# AEGIS_Junction_Box.net
KiCad netlist of a schematic drawn in Altium Designer
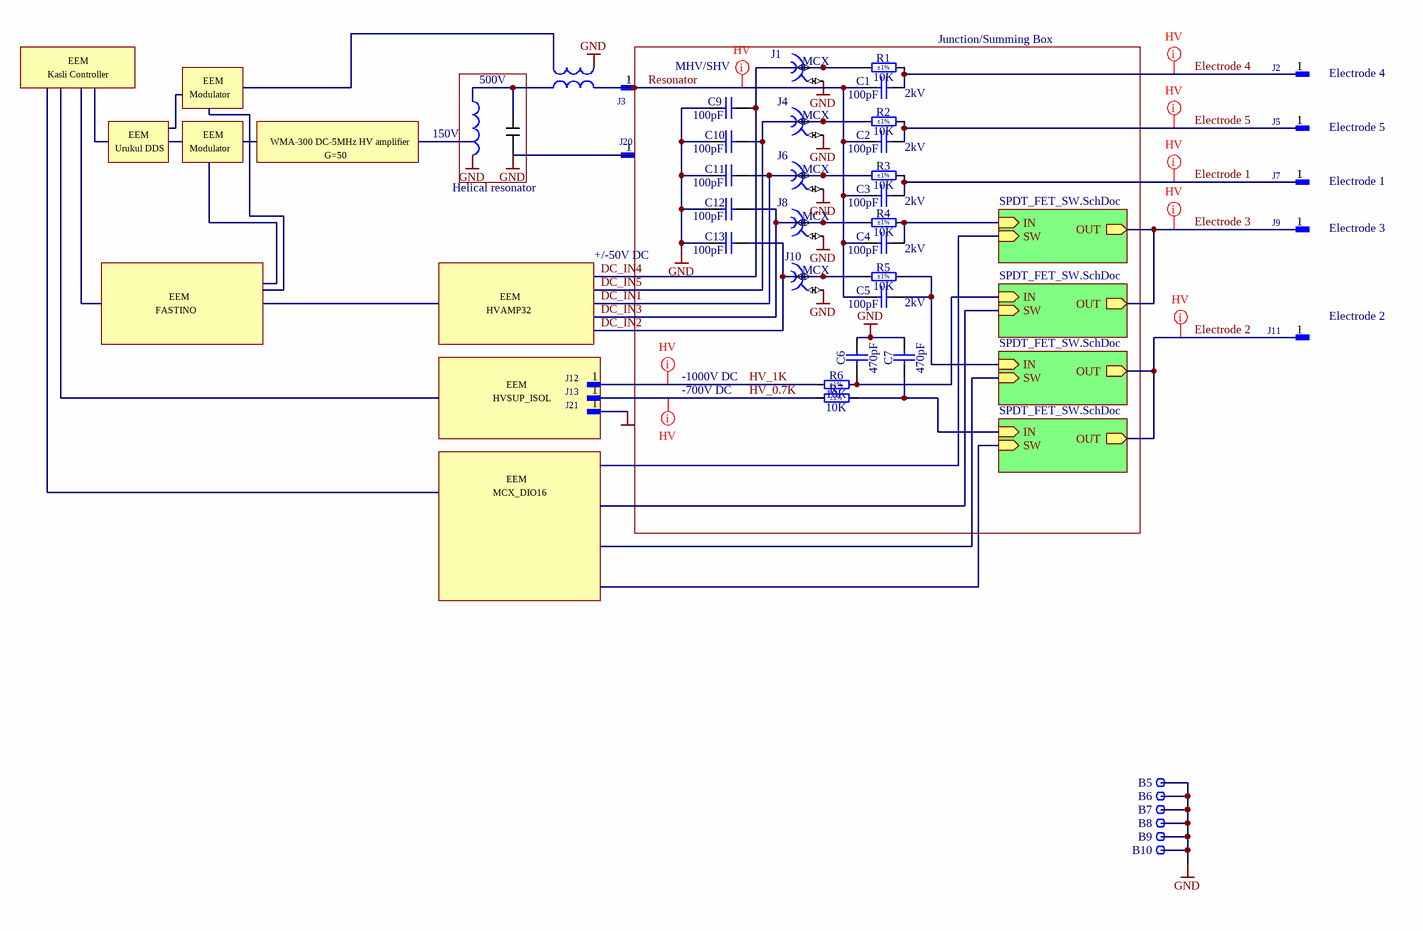
[diagram p0: AEGIS_Junction_Box.SchDoc]

(export (version "E")
  (design (tool "Eeschema 10.0.6"))
  (components
    (comp (ref "B5")
      (value "Plated Hole")
      (footprint "MTG320_550")
      (description "Single Terminal Socket")
      (fields (field (name "PART NUMBER") "PLATED_HOLE3.2_PAD5.5") (field (name "AUTHOR") "CERN DEM JMW"))
      (libsource (lib "Eletro-mechanical") (part "Single Terminal Socket"))
    )
    (comp (ref "B6")
      (value "Plated Hole")
      (footprint "MTG320_550")
      (description "Single Terminal Socket")
      (fields (field (name "PART NUMBER") "PLATED_HOLE3.2_PAD5.5") (field (name "AUTHOR") "CERN DEM JMW"))
      (libsource (lib "Eletro-mechanical") (part "Single Terminal Socket"))
    )
    (comp (ref "B7")
      (value "Plated Hole")
      (footprint "MTG320_550")
      (description "Single Terminal Socket")
      (fields (field (name "PART NUMBER") "PLATED_HOLE3.2_PAD5.5") (field (name "AUTHOR") "CERN DEM JMW"))
      (libsource (lib "Eletro-mechanical") (part "Single Terminal Socket"))
    )
    (comp (ref "B8")
      (value "Plated Hole")
      (footprint "MTG320_550")
      (description "Single Terminal Socket")
      (fields (field (name "PART NUMBER") "PLATED_HOLE3.2_PAD5.5") (field (name "AUTHOR") "CERN DEM JMW"))
      (libsource (lib "Eletro-mechanical") (part "Single Terminal Socket"))
    )
    (comp (ref "B9")
      (value "Plated Hole")
      (footprint "MTG320_550")
      (description "Single Terminal Socket")
      (fields (field (name "PART NUMBER") "PLATED_HOLE3.2_PAD5.5") (field (name "AUTHOR") "CERN DEM JMW"))
      (libsource (lib "Eletro-mechanical") (part "Single Terminal Socket"))
    )
    (comp (ref "B10")
      (value "Plated Hole")
      (footprint "MTG320_550")
      (description "Single Terminal Socket")
      (fields (field (name "PART NUMBER") "PLATED_HOLE3.2_PAD5.5") (field (name "AUTHOR") "CERN DEM JMW"))
      (libsource (lib "Eletro-mechanical") (part "Single Terminal Socket"))
    )
    (comp (ref "C1")
      (value "100pF")
      (footprint "CAPC3216X180N")
      (description "Non-polarised capacitor")
      (fields
        (field (name "PART NUMBER") "CC1206_100PF_2KV_5%_C0G")
        (field (name "VOLTAGE") "2kV")
        (field (name "TOLERANCE") "±5%")
        (field (name "AUTHOR") "CERN DEM JLC")
      )
      (libsource (lib "Capacitors") (part "Capacitor - non polarized"))
    )
    (comp (ref "C2")
      (value "100pF")
      (footprint "CAPC3216X180N")
      (description "Non-polarised capacitor")
      (fields
        (field (name "PART NUMBER") "CC1206_100PF_2KV_5%_C0G")
        (field (name "VOLTAGE") "2kV")
        (field (name "TOLERANCE") "±5%")
        (field (name "AUTHOR") "CERN DEM JLC")
      )
      (libsource (lib "Capacitors") (part "Capacitor - non polarized"))
    )
    (comp (ref "C3")
      (value "100pF")
      (footprint "CAPC3216X180N")
      (description "Non-polarised capacitor")
      (fields
        (field (name "PART NUMBER") "CC1206_100PF_2KV_5%_C0G")
        (field (name "VOLTAGE") "2kV")
        (field (name "TOLERANCE") "±5%")
        (field (name "AUTHOR") "CERN DEM JLC")
      )
      (libsource (lib "Capacitors") (part "Capacitor - non polarized"))
    )
    (comp (ref "C4")
      (value "100pF")
      (footprint "CAPC3216X180N")
      (description "Non-polarised capacitor")
      (fields
        (field (name "PART NUMBER") "CC1206_100PF_2KV_5%_C0G")
        (field (name "VOLTAGE") "2kV")
        (field (name "TOLERANCE") "±5%")
        (field (name "AUTHOR") "CERN DEM JLC")
      )
      (libsource (lib "Capacitors") (part "Capacitor - non polarized"))
    )
    (comp (ref "C5")
      (value "100pF")
      (footprint "CAPC3216X180N")
      (description "Non-polarised capacitor")
      (fields
        (field (name "PART NUMBER") "CC1206_100PF_2KV_5%_C0G")
        (field (name "VOLTAGE") "2kV")
        (field (name "TOLERANCE") "±5%")
        (field (name "AUTHOR") "CERN DEM JLC")
      )
      (libsource (lib "Capacitors") (part "Capacitor - non polarized"))
    )
    (comp (ref "C6")
      (value "470pF")
      (footprint "CAPC4520X150N")
      (description "Non-polarised capacitor")
      (fields
        (field (name "PART NUMBER") "CC1808_470PF_2KV_20%_X7R_TDK_CGA7K1X7R3D471M130KA")
        (field (name "VOLTAGE") "2kV")
        (field (name "AUTHOR") "CERN DEM JLC")
      )
      (libsource (lib "Capacitors") (part "Capacitor - non polarized"))
    )
    (comp (ref "C7")
      (value "470pF")
      (footprint "CAPC4520X150N")
      (description "Non-polarised capacitor")
      (fields
        (field (name "PART NUMBER") "CC1808_470PF_2KV_20%_X7R_TDK_CGA7K1X7R3D471M130KA")
        (field (name "VOLTAGE") "2kV")
        (field (name "AUTHOR") "CERN DEM JLC")
      )
      (libsource (lib "Capacitors") (part "Capacitor - non polarized"))
    )
    (comp (ref "C9")
      (value "100pF")
      (footprint "CAPC2012X135N")
      (description "Non-polarised capacitor")
      (fields
        (field (name "PART NUMBER") "CC0805_100PF_50V_5%_NP0")
        (field (name "VOLTAGE") "50V")
        (field (name "AUTHOR") "CERN DEM JLC")
      )
      (libsource (lib "Capacitors") (part "Capacitor - non polarized"))
    )
    (comp (ref "C10")
      (value "100pF")
      (footprint "CAPC2012X135N")
      (description "Non-polarised capacitor")
      (fields
        (field (name "PART NUMBER") "CC0805_100PF_50V_5%_NP0")
        (field (name "VOLTAGE") "50V")
        (field (name "AUTHOR") "CERN DEM JLC")
      )
      (libsource (lib "Capacitors") (part "Capacitor - non polarized"))
    )
    (comp (ref "C11")
      (value "100pF")
      (footprint "CAPC2012X135N")
      (description "Non-polarised capacitor")
      (fields
        (field (name "PART NUMBER") "CC0805_100PF_50V_5%_NP0")
        (field (name "VOLTAGE") "50V")
        (field (name "AUTHOR") "CERN DEM JLC")
      )
      (libsource (lib "Capacitors") (part "Capacitor - non polarized"))
    )
    (comp (ref "C12")
      (value "100pF")
      (footprint "CAPC2012X135N")
      (description "Non-polarised capacitor")
      (fields
        (field (name "PART NUMBER") "CC0805_100PF_50V_5%_NP0")
        (field (name "VOLTAGE") "50V")
        (field (name "AUTHOR") "CERN DEM JLC")
      )
      (libsource (lib "Capacitors") (part "Capacitor - non polarized"))
    )
    (comp (ref "C13")
      (value "100pF")
      (footprint "CAPC2012X135N")
      (description "Non-polarised capacitor")
      (fields
        (field (name "PART NUMBER") "CC0805_100PF_50V_5%_NP0")
        (field (name "VOLTAGE") "50V")
        (field (name "AUTHOR") "CERN DEM JLC")
      )
      (libsource (lib "Capacitors") (part "Capacitor - non polarized"))
    )
    (comp (ref "J1")
      (value "MCX")
      (footprint "AMPHENOL_919-383J-51A")
      (fields
        (field (name "PART NUMBER") "AMPHENOL_919-383J-51A")
        (field (name "MANUFACTURER") "AMPHENOL")
        (field (name "MANUFACTURER PART NUMBER") "919-383J-51A")
        (field (name "AUTHOR") "CERN DEM BC")
      )
      (libsource (lib "Connectors") (part "Coax_1Female_1Shield"))
    )
    (comp (ref "J2")
      (value "SMD Pad")
      (footprint "R400X300")
      (description "Single SMD Pad")
      (fields (field (name "PART NUMBER") "SMD_PAD_4X3MM") (field (name "AUTHOR") "CERN DEM JLC"))
      (libsource (lib "Eletro-mechanical") (part "Single SMD Pad"))
    )
    (comp (ref "J3")
      (value "SMD Pad")
      (footprint "R400X300")
      (description "Single SMD Pad")
      (fields (field (name "PART NUMBER") "SMD_PAD_4X3MM") (field (name "AUTHOR") "CERN DEM JLC"))
      (libsource (lib "") (part "Single SMD Pad_1"))
    )
    (comp (ref "J4")
      (value "MCX")
      (footprint "AMPHENOL_919-383J-51A")
      (fields
        (field (name "PART NUMBER") "AMPHENOL_919-383J-51A")
        (field (name "MANUFACTURER") "AMPHENOL")
        (field (name "MANUFACTURER PART NUMBER") "919-383J-51A")
        (field (name "AUTHOR") "CERN DEM BC")
      )
      (libsource (lib "Connectors") (part "Coax_1Female_1Shield"))
    )
    (comp (ref "J5")
      (value "SMD Pad")
      (footprint "R400X300")
      (description "Single SMD Pad")
      (fields (field (name "PART NUMBER") "SMD_PAD_4X3MM") (field (name "AUTHOR") "CERN DEM JLC"))
      (libsource (lib "Eletro-mechanical") (part "Single SMD Pad"))
    )
    (comp (ref "J6")
      (value "MCX")
      (footprint "AMPHENOL_919-383J-51A")
      (fields
        (field (name "PART NUMBER") "AMPHENOL_919-383J-51A")
        (field (name "MANUFACTURER") "AMPHENOL")
        (field (name "MANUFACTURER PART NUMBER") "919-383J-51A")
        (field (name "AUTHOR") "CERN DEM BC")
      )
      (libsource (lib "Connectors") (part "Coax_1Female_1Shield"))
    )
    (comp (ref "J7")
      (value "SMD Pad")
      (footprint "R400X300")
      (description "Single SMD Pad")
      (fields (field (name "PART NUMBER") "SMD_PAD_4X3MM") (field (name "AUTHOR") "CERN DEM JLC"))
      (libsource (lib "Eletro-mechanical") (part "Single SMD Pad"))
    )
    (comp (ref "J8")
      (value "MCX")
      (footprint "AMPHENOL_919-383J-51A")
      (fields
        (field (name "PART NUMBER") "AMPHENOL_919-383J-51A")
        (field (name "MANUFACTURER") "AMPHENOL")
        (field (name "MANUFACTURER PART NUMBER") "919-383J-51A")
        (field (name "AUTHOR") "CERN DEM BC")
      )
      (libsource (lib "Connectors") (part "Coax_1Female_1Shield"))
    )
    (comp (ref "J9")
      (value "SMD Pad")
      (footprint "R400X300")
      (description "Single SMD Pad")
      (fields (field (name "PART NUMBER") "SMD_PAD_4X3MM") (field (name "AUTHOR") "CERN DEM JLC"))
      (libsource (lib "Eletro-mechanical") (part "Single SMD Pad"))
    )
    (comp (ref "J10")
      (value "MCX")
      (footprint "AMPHENOL_919-383J-51A")
      (fields
        (field (name "PART NUMBER") "AMPHENOL_919-383J-51A")
        (field (name "MANUFACTURER") "AMPHENOL")
        (field (name "MANUFACTURER PART NUMBER") "919-383J-51A")
        (field (name "AUTHOR") "CERN DEM BC")
      )
      (libsource (lib "Connectors") (part "Coax_1Female_1Shield"))
    )
    (comp (ref "J11")
      (value "SMD Pad")
      (footprint "R400X300")
      (description "Single SMD Pad")
      (fields (field (name "PART NUMBER") "SMD_PAD_4X3MM") (field (name "AUTHOR") "CERN DEM JLC"))
      (libsource (lib "Eletro-mechanical") (part "Single SMD Pad"))
    )
    (comp (ref "J12")
      (value "SMD Pad")
      (footprint "R400X300")
      (description "Single SMD Pad")
      (fields (field (name "PART NUMBER") "SMD_PAD_4X3MM") (field (name "AUTHOR") "CERN DEM JLC"))
      (libsource (lib "") (part "Single SMD Pad_1"))
    )
    (comp (ref "J13")
      (value "SMD Pad")
      (footprint "R400X300")
      (description "Single SMD Pad")
      (fields (field (name "PART NUMBER") "SMD_PAD_4X3MM") (field (name "AUTHOR") "CERN DEM JLC"))
      (libsource (lib "") (part "Single SMD Pad_1"))
    )
    (comp (ref "J20")
      (value "SMD Pad")
      (footprint "R400X300")
      (description "Single SMD Pad")
      (fields (field (name "PART NUMBER") "SMD_PAD_4X3MM") (field (name "AUTHOR") "CERN DEM JLC"))
      (libsource (lib "") (part "Single SMD Pad_1"))
    )
    (comp (ref "J21")
      (value "SMD Pad")
      (footprint "R400X300")
      (description "Single SMD Pad")
      (fields (field (name "PART NUMBER") "SMD_PAD_4X3MM") (field (name "AUTHOR") "CERN DEM JLC"))
      (libsource (lib "") (part "Single SMD Pad_1"))
    )
    (comp (ref "R1")
      (value "10K")
      (footprint "RESC6532X80N")
      (description "High Voltage (3kV) Chip Resistor")
      (fields
        (field (name "PART NUMBER") "R2512_10k_1%_1W_100PPM")
        (field (name "POWER") "1W")
        (field (name "TOLERANCE") "±1%")
        (field (name "AUTHOR") "GK")
      )
      (libsource (lib "Passives_RC") (part "R2512_10k_1%_1W_100PPM"))
    )
    (comp (ref "R2")
      (value "10K")
      (footprint "RESC6532X80N")
      (description "High Voltage (3kV) Chip Resistor")
      (fields
        (field (name "PART NUMBER") "R2512_10k_1%_1W_100PPM")
        (field (name "POWER") "1W")
        (field (name "TOLERANCE") "±1%")
        (field (name "AUTHOR") "GK")
      )
      (libsource (lib "Passives_RC") (part "R2512_10k_1%_1W_100PPM"))
    )
    (comp (ref "R3")
      (value "10K")
      (footprint "RESC6532X80N")
      (description "High Voltage (3kV) Chip Resistor")
      (fields
        (field (name "PART NUMBER") "R2512_10k_1%_1W_100PPM")
        (field (name "POWER") "1W")
        (field (name "TOLERANCE") "±1%")
        (field (name "AUTHOR") "GK")
      )
      (libsource (lib "Passives_RC") (part "R2512_10k_1%_1W_100PPM"))
    )
    (comp (ref "R4")
      (value "10K")
      (footprint "RESC6532X80N")
      (description "High Voltage (3kV) Chip Resistor")
      (fields
        (field (name "PART NUMBER") "R2512_10k_1%_1W_100PPM")
        (field (name "POWER") "1W")
        (field (name "TOLERANCE") "±1%")
        (field (name "AUTHOR") "GK")
      )
      (libsource (lib "Passives_RC") (part "R2512_10k_1%_1W_100PPM"))
    )
    (comp (ref "R5")
      (value "10K")
      (footprint "RESC6532X80N")
      (description "High Voltage (3kV) Chip Resistor")
      (fields
        (field (name "PART NUMBER") "R2512_10k_1%_1W_100PPM")
        (field (name "POWER") "1W")
        (field (name "TOLERANCE") "±1%")
        (field (name "AUTHOR") "GK")
      )
      (libsource (lib "Passives_RC") (part "R2512_10k_1%_1W_100PPM"))
    )
    (comp (ref "R6")
      (value "10K")
      (footprint "RESC6532X80N")
      (description "High Voltage (3kV) Chip Resistor")
      (fields
        (field (name "PART NUMBER") "R2512_10k_1%_1W_100PPM")
        (field (name "POWER") "1W")
        (field (name "TOLERANCE") "±1%")
        (field (name "AUTHOR") "GK")
      )
      (libsource (lib "Passives_RC") (part "R2512_10k_1%_1W_100PPM"))
    )
    (comp (ref "R7")
      (value "10K")
      (footprint "RESC6532X80N")
      (description "High Voltage (3kV) Chip Resistor")
      (fields
        (field (name "PART NUMBER") "R2512_10k_1%_1W_100PPM")
        (field (name "POWER") "1W")
        (field (name "TOLERANCE") "±1%")
        (field (name "AUTHOR") "GK")
      )
      (libsource (lib "Passives_RC") (part "R2512_10k_1%_1W_100PPM"))
    )
  )
  (nets
    (net (code "1") (name "/DC_IN1") (class "Default")
      (node (ref "C11") (pin "2") (pinfunction "2_2") (pintype "passive"))
      (node (ref "J6") (pin "1") (pinfunction "1_1") (pintype "bidirectional"))
      (node (ref "R3") (pin "1") (pinfunction "1_1") (pintype "passive"))
    )
    (net (code "2") (name "/DC_IN2") (class "Default")
      (node (ref "C13") (pin "2") (pinfunction "2_2") (pintype "passive"))
      (node (ref "J10") (pin "1") (pinfunction "1_1") (pintype "bidirectional"))
      (node (ref "R5") (pin "1") (pinfunction "1_1") (pintype "passive"))
    )
    (net (code "3") (name "/DC_IN3") (class "Default")
      (node (ref "C12") (pin "2") (pinfunction "2_2") (pintype "passive"))
      (node (ref "J8") (pin "1") (pinfunction "1_1") (pintype "bidirectional"))
      (node (ref "R4") (pin "1") (pinfunction "1_1") (pintype "passive"))
    )
    (net (code "4") (name "/DC_IN4") (class "Default")
      (node (ref "C9") (pin "2") (pinfunction "2_2") (pintype "passive"))
      (node (ref "J1") (pin "1") (pinfunction "1_1") (pintype "bidirectional"))
      (node (ref "R1") (pin "1") (pinfunction "1_1") (pintype "passive"))
    )
    (net (code "5") (name "/DC_IN5") (class "Default")
      (node (ref "C10") (pin "2") (pinfunction "2_2") (pintype "passive"))
      (node (ref "J4") (pin "1") (pinfunction "1_1") (pintype "bidirectional"))
      (node (ref "R2") (pin "1") (pinfunction "1_1") (pintype "passive"))
    )
    (net (code "6") (name "/Electrode 1") (class "Default")
      (node (ref "C3") (pin "2") (pinfunction "2_2") (pintype "passive"))
      (node (ref "J7") (pin "1") (pinfunction "1_1") (pintype "bidirectional"))
      (node (ref "R3") (pin "2") (pinfunction "2_2") (pintype "passive"))
    )
    (net (code "7") (name "/Electrode 2") (class "Default")
      (node (ref "J11") (pin "1") (pinfunction "1_1") (pintype "bidirectional"))
    )
    (net (code "8") (name "/Electrode 3") (class "Default")
      (node (ref "J9") (pin "1") (pinfunction "1_1") (pintype "bidirectional"))
    )
    (net (code "9") (name "/Electrode 4") (class "Default")
      (node (ref "C1") (pin "2") (pinfunction "2_2") (pintype "passive"))
      (node (ref "J2") (pin "1") (pinfunction "1_1") (pintype "bidirectional"))
      (node (ref "R1") (pin "2") (pinfunction "2_2") (pintype "passive"))
    )
    (net (code "10") (name "/Electrode 5") (class "Default")
      (node (ref "C2") (pin "2") (pinfunction "2_2") (pintype "passive"))
      (node (ref "J5") (pin "1") (pinfunction "1_1") (pintype "bidirectional"))
      (node (ref "R2") (pin "2") (pinfunction "2_2") (pintype "passive"))
    )
    (net (code "11") (name "/HV_0.7K") (class "Default")
      (node (ref "J13") (pin "1") (pinfunction "1_1") (pintype "bidirectional"))
      (node (ref "R7") (pin "1") (pinfunction "1_1") (pintype "passive"))
    )
    (net (code "12") (name "/HV_1K") (class "Default")
      (node (ref "J12") (pin "1") (pinfunction "1_1") (pintype "bidirectional"))
      (node (ref "R6") (pin "1") (pinfunction "1_1") (pintype "passive"))
    )
    (net (code "13") (name "/IN") (class "Default")
      (node (ref "C7") (pin "1") (pinfunction "1_1") (pintype "passive"))
      (node (ref "R7") (pin "2") (pinfunction "2_2") (pintype "passive"))
    )
    (net (code "14") (name "/IN_1") (class "Default")
      (node (ref "C4") (pin "2") (pinfunction "2_2") (pintype "passive"))
      (node (ref "R4") (pin "2") (pinfunction "2_2") (pintype "passive"))
    )
    (net (code "15") (name "/IN_2") (class "Default")
      (node (ref "C6") (pin "1") (pinfunction "1_1") (pintype "passive"))
      (node (ref "R6") (pin "2") (pinfunction "2_2") (pintype "passive"))
    )
    (net (code "16") (name "/IN_3") (class "Default")
      (node (ref "C5") (pin "2") (pinfunction "2_2") (pintype "passive"))
      (node (ref "R5") (pin "2") (pinfunction "2_2") (pintype "passive"))
    )
    (net (code "17") (name "/Resonator") (class "Default")
      (node (ref "C1") (pin "1") (pinfunction "1_1") (pintype "passive"))
      (node (ref "C2") (pin "1") (pinfunction "1_1") (pintype "passive"))
      (node (ref "C3") (pin "1") (pinfunction "1_1") (pintype "passive"))
      (node (ref "C4") (pin "1") (pinfunction "1_1") (pintype "passive"))
      (node (ref "C5") (pin "1") (pinfunction "1_1") (pintype "passive"))
      (node (ref "J3") (pin "1") (pinfunction "1_1") (pintype "bidirectional"))
    )
    (net (code "22") (name "GND") (class "Default")
      (node (ref "B10") (pin "1") (pinfunction "1_1") (pintype "bidirectional"))
      (node (ref "B5") (pin "1") (pinfunction "1_1") (pintype "bidirectional"))
      (node (ref "B6") (pin "1") (pinfunction "1_1") (pintype "bidirectional"))
      (node (ref "B7") (pin "1") (pinfunction "1_1") (pintype "bidirectional"))
      (node (ref "B8") (pin "1") (pinfunction "1_1") (pintype "bidirectional"))
      (node (ref "B9") (pin "1") (pinfunction "1_1") (pintype "bidirectional"))
      (node (ref "C10") (pin "1") (pinfunction "1_1") (pintype "passive"))
      (node (ref "C11") (pin "1") (pinfunction "1_1") (pintype "passive"))
      (node (ref "C12") (pin "1") (pinfunction "1_1") (pintype "passive"))
      (node (ref "C13") (pin "1") (pinfunction "1_1") (pintype "passive"))
      (node (ref "C6") (pin "2") (pinfunction "2_2") (pintype "passive"))
      (node (ref "C7") (pin "2") (pinfunction "2_2") (pintype "passive"))
      (node (ref "C9") (pin "1") (pinfunction "1_1") (pintype "passive"))
      (node (ref "J1") (pin "2") (pinfunction "2_2") (pintype "bidirectional"))
      (node (ref "J10") (pin "2") (pinfunction "2_2") (pintype "bidirectional"))
      (node (ref "J20") (pin "1") (pinfunction "1_1") (pintype "bidirectional"))
      (node (ref "J21") (pin "1") (pinfunction "1_1") (pintype "bidirectional"))
      (node (ref "J4") (pin "2") (pinfunction "2_2") (pintype "bidirectional"))
      (node (ref "J6") (pin "2") (pinfunction "2_2") (pintype "bidirectional"))
      (node (ref "J8") (pin "2") (pinfunction "2_2") (pintype "bidirectional"))
    )
  )
)
